# OMHOT.net
KiCad netlist of a schematic drawn in EAGLE
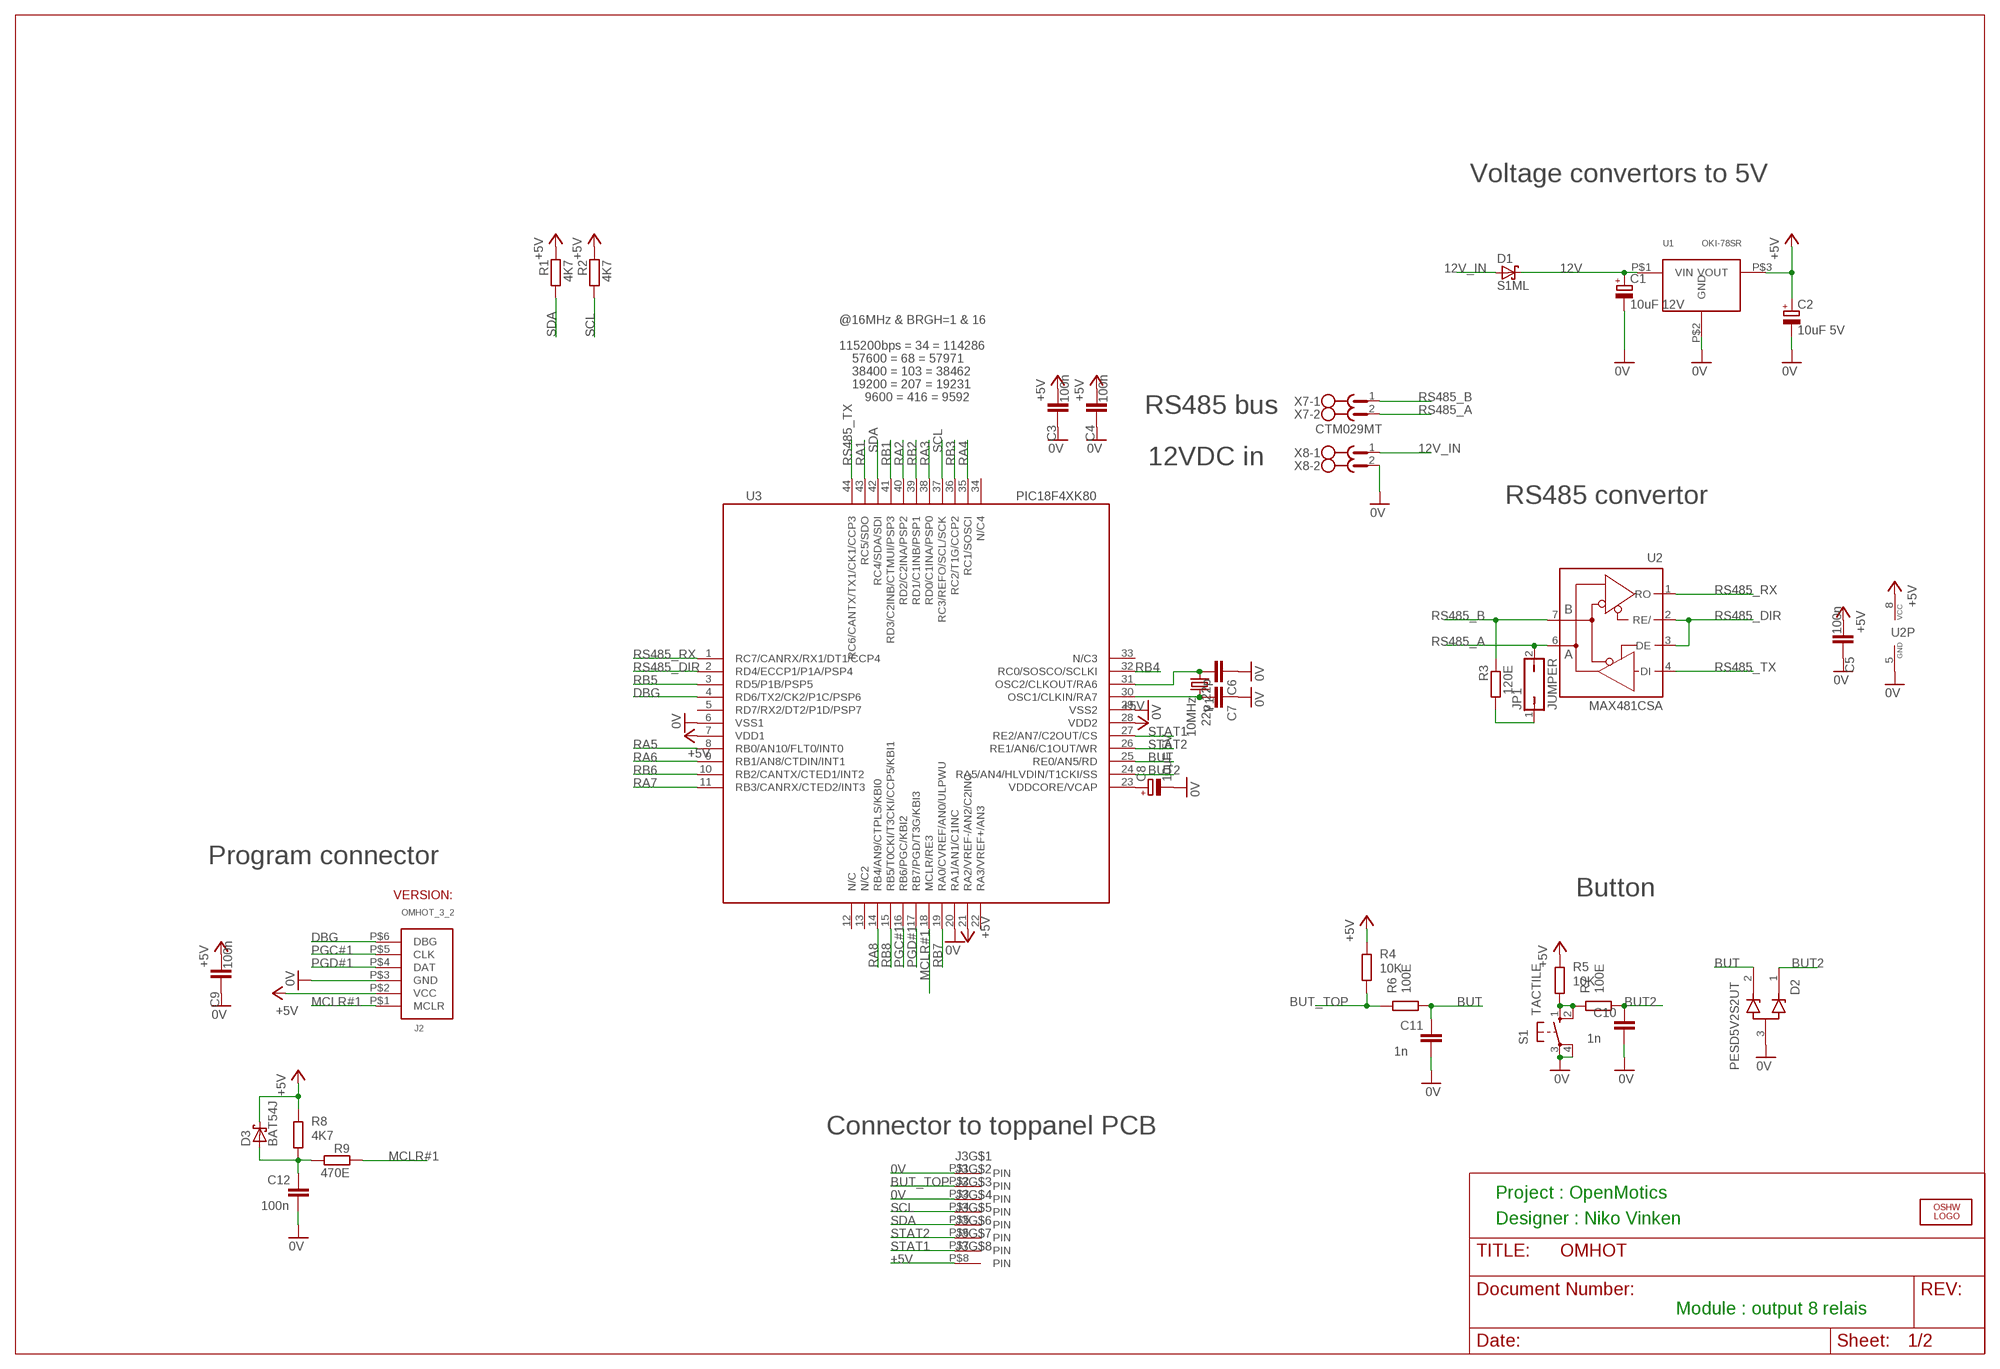
[diagram p0: schematic, sheet 1]
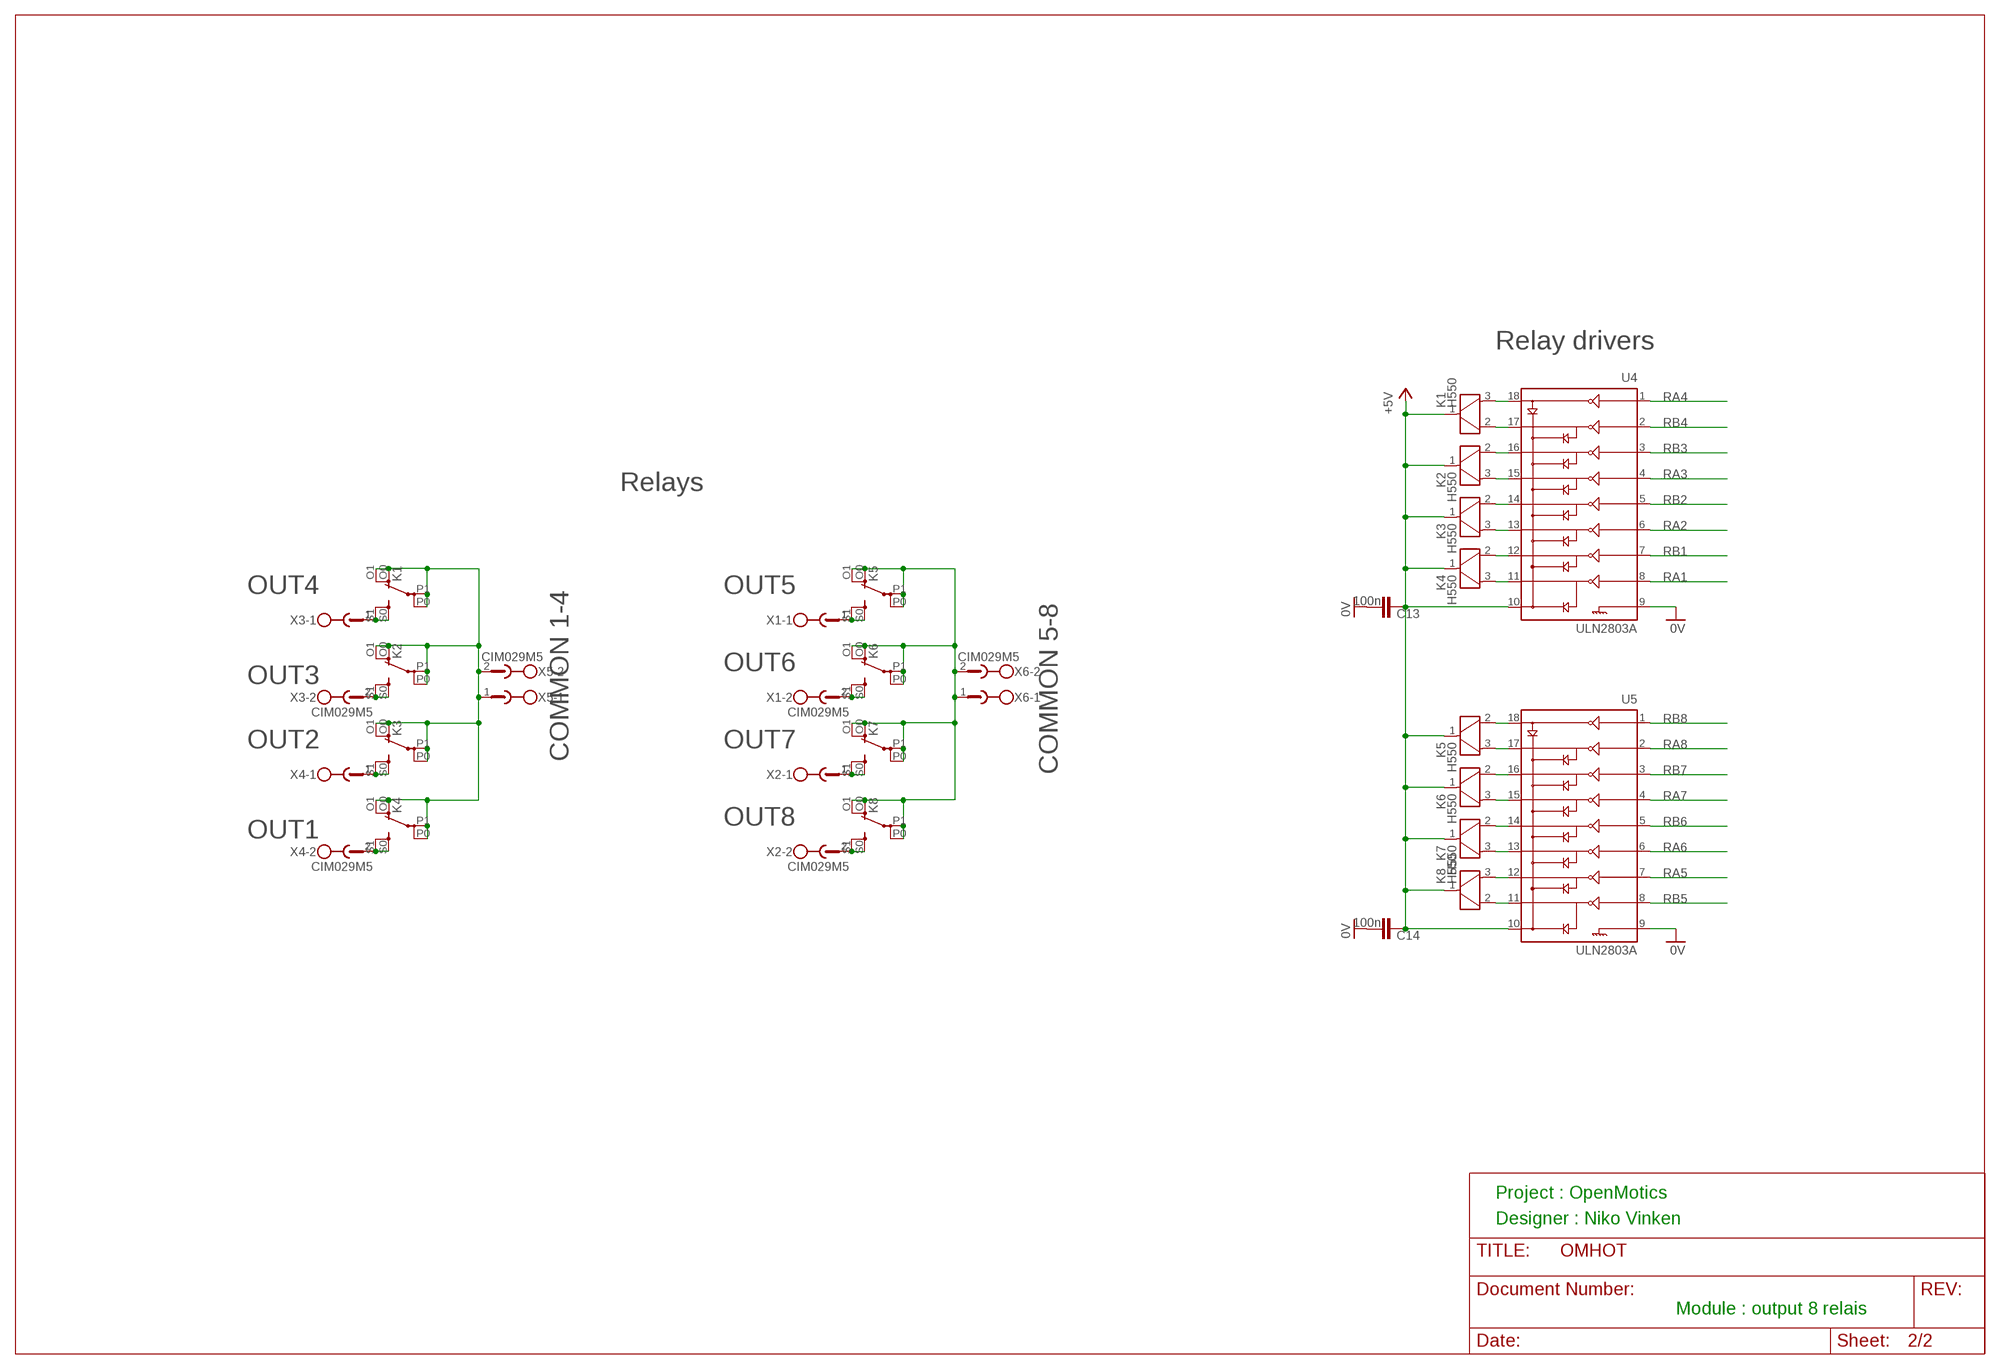
[diagram p1: schematic, sheet 2]

(export (version "E")
  (design (tool "Eeschema 10.0.6"))
  (components
    (comp (ref "C13")
      (value "100n")
      (footprint "eagle-import:C0603")
      (libsource (lib "eagle-import") (part "C-EUC0603"))
    )
    (comp (ref "C14")
      (value "100n")
      (footprint "eagle-import:C0603")
      (libsource (lib "eagle-import") (part "C-EUC0603"))
    )
    (comp (ref "K1")
      (value "H550")
      (footprint "eagle-import:H550")
      (libsource (lib "eagle-import") (part "H550"))
    )
    (comp (ref "K2")
      (value "H550")
      (footprint "eagle-import:H550")
      (libsource (lib "eagle-import") (part "H550"))
    )
    (comp (ref "K3")
      (value "H550")
      (footprint "eagle-import:H550")
      (libsource (lib "eagle-import") (part "H550"))
    )
    (comp (ref "K4")
      (value "H550")
      (footprint "eagle-import:H550")
      (libsource (lib "eagle-import") (part "H550"))
    )
    (comp (ref "K5")
      (value "H550")
      (footprint "eagle-import:H550")
      (libsource (lib "eagle-import") (part "H550"))
    )
    (comp (ref "K6")
      (value "H550")
      (footprint "eagle-import:H550")
      (libsource (lib "eagle-import") (part "H550"))
    )
    (comp (ref "K7")
      (value "H550")
      (footprint "eagle-import:H550")
      (libsource (lib "eagle-import") (part "H550"))
    )
    (comp (ref "K8")
      (value "H550")
      (footprint "eagle-import:H550")
      (libsource (lib "eagle-import") (part "H550"))
    )
    (comp (ref "U4")
      (value "ULN2803A")
      (footprint "eagle-import:SOIC18")
      (libsource (lib "eagle-import") (part "ULN2803A"))
    )
    (comp (ref "U5")
      (value "ULN2803A")
      (footprint "eagle-import:SOIC18")
      (libsource (lib "eagle-import") (part "ULN2803A"))
    )
    (comp (ref "X1")
      (value "CIM029M5")
      (footprint "eagle-import:CIM029M5")
      (fields (field (name "MF") "SAURO"))
      (libsource (lib "eagle-import") (part "CIM029M5"))
    )
    (comp (ref "X2")
      (value "CIM029M5")
      (footprint "eagle-import:CIM029M5")
      (fields (field (name "MF") "SAURO"))
      (libsource (lib "eagle-import") (part "CIM029M5"))
    )
    (comp (ref "X3")
      (value "CIM029M5")
      (footprint "eagle-import:CIM029M5")
      (fields (field (name "MF") "SAURO"))
      (libsource (lib "eagle-import") (part "CIM029M5"))
    )
    (comp (ref "X4")
      (value "CIM029M5")
      (footprint "eagle-import:CIM029M5")
      (fields (field (name "MF") "SAURO"))
      (libsource (lib "eagle-import") (part "CIM029M5"))
    )
    (comp (ref "X5")
      (value "CIM029M5")
      (footprint "eagle-import:CIM029M5")
      (fields (field (name "MF") "SAURO"))
      (libsource (lib "eagle-import") (part "CIM029M5"))
    )
    (comp (ref "X6")
      (value "CIM029M5")
      (footprint "eagle-import:CIM029M5")
      (fields (field (name "MF") "SAURO"))
      (libsource (lib "eagle-import") (part "CIM029M5"))
    )
    (comp (ref "C1")
      (value "10uF 12V")
      (footprint "eagle-import:085CS_1AR")
      (libsource (lib "eagle-import") (part "CPOL-EU085CS-1AR"))
    )
    (comp (ref "C2")
      (value "10uF 5V")
      (footprint "eagle-import:085CS_1AR")
      (libsource (lib "eagle-import") (part "CPOL-EU085CS-1AR"))
    )
    (comp (ref "C3")
      (value "100n")
      (footprint "eagle-import:C0603")
      (libsource (lib "eagle-import") (part "C-EUC0603"))
    )
    (comp (ref "C4")
      (value "100n")
      (footprint "eagle-import:C0603")
      (libsource (lib "eagle-import") (part "C-EUC0603"))
    )
    (comp (ref "C5")
      (value "100n")
      (footprint "eagle-import:C0603")
      (libsource (lib "eagle-import") (part "C-EUC0603"))
    )
    (comp (ref "C6")
      (value "22p")
      (footprint "eagle-import:C0603")
      (libsource (lib "eagle-import") (part "C-EUC0603"))
    )
    (comp (ref "C7")
      (value "22p")
      (footprint "eagle-import:C0603")
      (libsource (lib "eagle-import") (part "C-EUC0603"))
    )
    (comp (ref "C8")
      (value "10uF 5V")
      (footprint "eagle-import:085CS_1AR")
      (libsource (lib "eagle-import") (part "CPOL-EU085CS-1AR"))
    )
    (comp (ref "C9")
      (value "100n")
      (footprint "eagle-import:C0603")
      (libsource (lib "eagle-import") (part "C-EUC0603"))
    )
    (comp (ref "C10")
      (value "1n")
      (footprint "eagle-import:C0603")
      (libsource (lib "eagle-import") (part "C-EUC0603"))
    )
    (comp (ref "C11")
      (value "1n")
      (footprint "eagle-import:C0603")
      (libsource (lib "eagle-import") (part "C-EUC0603"))
    )
    (comp (ref "C12")
      (value "100n")
      (footprint "eagle-import:C0603")
      (libsource (lib "eagle-import") (part "C-EUC0603"))
    )
    (comp (ref "D1")
      (value "S1ML")
      (footprint "eagle-import:SOD123FL")
      (libsource (lib "eagle-import") (part "SMF5.0AT1"))
    )
    (comp (ref "D2")
      (value "PESD5V2S2UT")
      (footprint "eagle-import:SOT23")
      (libsource (lib "eagle-import") (part "PESD3V3S2UAT"))
    )
    (comp (ref "D3")
      (value "BAT54J")
      (footprint "eagle-import:SOD323_REFLOW")
      (libsource (lib "eagle-import") (part "BAT54J"))
    )
    (comp (ref "J2")
      (value "PROG_CON")
      (footprint "eagle-import:PROG_CON_WITH_VERSION")
      (fields (field (name "VERSION") "OMHOT_3_2"))
      (libsource (lib "eagle-import") (part "PROG_CON"))
    )
    (comp (ref "J3")
      (value "8PIN_CON_AMP")
      (footprint "eagle-import:8PIN_CON_AMP")
      (libsource (lib "eagle-import") (part "8PIN_CON_AMP"))
    )
    (comp (ref "JP1")
      (value "JUMPER")
      (footprint "eagle-import:JP1")
      (libsource (lib "eagle-import") (part "JP1Q"))
    )
    (comp (ref "LOGO2")
      (value "OSHW_LOGO_FILLX0150-NT")
      (footprint "eagle-import:OSHW_FILLX150_NOTEXT")
      (libsource (lib "eagle-import") (part "OSHW_LOGO_FILLX0150-NT"))
    )
    (comp (ref "R1")
      (value "4K7")
      (footprint "eagle-import:R0603")
      (libsource (lib "eagle-import") (part "R-EU_R0603"))
    )
    (comp (ref "R2")
      (value "4K7")
      (footprint "eagle-import:R0603")
      (libsource (lib "eagle-import") (part "R-EU_R0603"))
    )
    (comp (ref "R3")
      (value "120E")
      (footprint "eagle-import:R1206")
      (libsource (lib "eagle-import") (part "R-EU_R1206"))
    )
    (comp (ref "R4")
      (value "10K")
      (footprint "eagle-import:R0603")
      (libsource (lib "eagle-import") (part "R-EU_R0603"))
    )
    (comp (ref "R5")
      (value "10K")
      (footprint "eagle-import:R0603")
      (libsource (lib "eagle-import") (part "R-EU_R0603"))
    )
    (comp (ref "R6")
      (value "100E")
      (footprint "eagle-import:R0603")
      (libsource (lib "eagle-import") (part "R-EU_R0603"))
    )
    (comp (ref "R7")
      (value "100E")
      (footprint "eagle-import:R0603")
      (libsource (lib "eagle-import") (part "R-EU_R0603"))
    )
    (comp (ref "R8")
      (value "4K7")
      (footprint "eagle-import:R0603")
      (libsource (lib "eagle-import") (part "R-EU_R0603"))
    )
    (comp (ref "R9")
      (value "470E")
      (footprint "eagle-import:R0603")
      (libsource (lib "eagle-import") (part "R-EU_R0603"))
    )
    (comp (ref "S1")
      (value "TACTILE")
      (footprint "eagle-import:B3F-10XX")
      (fields (field (name "MPN") "B3F-1000"))
      (libsource (lib "eagle-import") (part "10-XX"))
    )
    (comp (ref "U1")
      (value "OKI-78SR")
      (footprint "eagle-import:OKI-78SR")
      (libsource (lib "eagle-import") (part "OKI-78SR"))
    )
    (comp (ref "U2")
      (value "MAX481CSA")
      (footprint "eagle-import:SO08")
      (fields (field (name "MF") "MAXIM"))
      (libsource (lib "eagle-import") (part "MAX481CSA"))
    )
    (comp (ref "U3")
      (value "PIC18F4XK80")
      (footprint "eagle-import:TQFP44")
      (libsource (lib "eagle-import") (part "PIC18F4XK80"))
    )
    (comp (ref "X7")
      (value "CTM029MT")
      (footprint "eagle-import:CTM029MT")
      (fields (field (name "MF") "SAURO"))
      (libsource (lib "eagle-import") (part "CTM029MT"))
    )
    (comp (ref "X8")
      (value "CTM029MT")
      (footprint "eagle-import:CTM029MT")
      (fields (field (name "MF") "SAURO"))
      (libsource (lib "eagle-import") (part "CTM029MT"))
    )
    (comp (ref "Y1")
      (value "10MHz")
      (footprint "eagle-import:SM49")
      (libsource (lib "eagle-import") (part "CRYSTALSM49"))
    )
  )
  (nets
    (net (code "1") (name "+5V") (class "Default")
      (node (ref "C13") (pin "2") (pinfunction "2_2") (pintype "passive"))
      (node (ref "C14") (pin "2") (pinfunction "2_2") (pintype "passive"))
      (node (ref "C2") (pin "+") (pinfunction "+_+") (pintype "passive"))
      (node (ref "C3") (pin "1") (pinfunction "1_1") (pintype "passive"))
      (node (ref "C4") (pin "1") (pinfunction "1_1") (pintype "passive"))
      (node (ref "C5") (pin "1") (pinfunction "1_1") (pintype "passive"))
      (node (ref "C9") (pin "1") (pinfunction "1_1") (pintype "passive"))
      (node (ref "D3") (pin "1") (pinfunction "1_1") (pintype "passive"))
      (node (ref "J2") (pin "P$2") (pinfunction "VCC_P$2") (pintype "bidirectional"))
      (node (ref "J3") (pin "P$8") (pinfunction "PIN_P$8") (pintype "bidirectional"))
      (node (ref "K1") (pin "1") (pinfunction "1_1") (pintype "passive"))
      (node (ref "K2") (pin "1") (pinfunction "1_1") (pintype "passive"))
      (node (ref "K3") (pin "1") (pinfunction "1_1") (pintype "passive"))
      (node (ref "K4") (pin "1") (pinfunction "1_1") (pintype "passive"))
      (node (ref "K5") (pin "1") (pinfunction "1_1") (pintype "passive"))
      (node (ref "K6") (pin "1") (pinfunction "1_1") (pintype "passive"))
      (node (ref "K7") (pin "1") (pinfunction "1_1") (pintype "passive"))
      (node (ref "K8") (pin "1") (pinfunction "1_1") (pintype "passive"))
      (node (ref "R1") (pin "1") (pinfunction "1_1") (pintype "passive"))
      (node (ref "R2") (pin "1") (pinfunction "1_1") (pintype "passive"))
      (node (ref "R4") (pin "2") (pinfunction "2_2") (pintype "passive"))
      (node (ref "R5") (pin "2") (pinfunction "2_2") (pintype "passive"))
      (node (ref "R8") (pin "2") (pinfunction "2_2") (pintype "passive"))
      (node (ref "U1") (pin "P$3") (pinfunction "VOUT_P$3") (pintype "bidirectional"))
      (node (ref "U2") (pin "8") (pinfunction "VCC_8") (pintype "power_in"))
      (node (ref "U3") (pin "21") (pinfunction "RA2/VREF-/AN2/C2INC_21") (pintype "bidirectional"))
      (node (ref "U3") (pin "28") (pinfunction "VDD2_28") (pintype "bidirectional"))
      (node (ref "U3") (pin "7") (pinfunction "VDD1_7") (pintype "bidirectional"))
      (node (ref "U4") (pin "10") (pinfunction "10_10") (pintype "bidirectional"))
      (node (ref "U5") (pin "10") (pinfunction "10_10") (pintype "bidirectional"))
    )
    (net (code "2") (name "0V") (class "Default")
      (node (ref "C1") (pin "-") (pinfunction "-_-") (pintype "passive"))
      (node (ref "C10") (pin "1") (pinfunction "1_1") (pintype "passive"))
      (node (ref "C11") (pin "1") (pinfunction "1_1") (pintype "passive"))
      (node (ref "C12") (pin "1") (pinfunction "1_1") (pintype "passive"))
      (node (ref "C13") (pin "1") (pinfunction "1_1") (pintype "passive"))
      (node (ref "C14") (pin "1") (pinfunction "1_1") (pintype "passive"))
      (node (ref "C2") (pin "-") (pinfunction "-_-") (pintype "passive"))
      (node (ref "C3") (pin "2") (pinfunction "2_2") (pintype "passive"))
      (node (ref "C4") (pin "2") (pinfunction "2_2") (pintype "passive"))
      (node (ref "C5") (pin "2") (pinfunction "2_2") (pintype "passive"))
      (node (ref "C6") (pin "1") (pinfunction "1_1") (pintype "passive"))
      (node (ref "C7") (pin "1") (pinfunction "1_1") (pintype "passive"))
      (node (ref "C8") (pin "-") (pinfunction "-_-") (pintype "passive"))
      (node (ref "C9") (pin "2") (pinfunction "2_2") (pintype "passive"))
      (node (ref "D2") (pin "3") (pinfunction "3_3") (pintype "bidirectional"))
      (node (ref "J2") (pin "P$3") (pinfunction "GND_P$3") (pintype "bidirectional"))
      (node (ref "J3") (pin "P$1") (pinfunction "PIN_P$1") (pintype "bidirectional"))
      (node (ref "J3") (pin "P$3") (pinfunction "PIN_P$3") (pintype "bidirectional"))
      (node (ref "S1") (pin "3") (pinfunction "P_3") (pintype "passive"))
      (node (ref "S1") (pin "4") (pinfunction "P1_4") (pintype "passive"))
      (node (ref "U1") (pin "P$2") (pinfunction "GND_P$2") (pintype "bidirectional"))
      (node (ref "U2") (pin "5") (pinfunction "GND_5") (pintype "power_in"))
      (node (ref "U3") (pin "20") (pinfunction "RA1/AN1/C1INC_20") (pintype "bidirectional"))
      (node (ref "U3") (pin "29") (pinfunction "VSS2_29") (pintype "bidirectional"))
      (node (ref "U3") (pin "6") (pinfunction "VSS1_6") (pintype "bidirectional"))
      (node (ref "U4") (pin "9") (pinfunction "9_9") (pintype "bidirectional"))
      (node (ref "U5") (pin "9") (pinfunction "9_9") (pintype "bidirectional"))
      (node (ref "X8") (pin "2") (pinfunction "1_2") (pintype "passive"))
    )
    (net (code "3") (name "12V") (class "Default")
      (node (ref "C1") (pin "+") (pinfunction "+_+") (pintype "passive"))
      (node (ref "D1") (pin "C") (pinfunction "C_C") (pintype "passive"))
      (node (ref "U1") (pin "P$1") (pinfunction "VIN_P$1") (pintype "bidirectional"))
    )
    (net (code "4") (name "12V_IN") (class "Default")
      (node (ref "D1") (pin "A") (pinfunction "A_A") (pintype "passive"))
      (node (ref "X8") (pin "1") (pinfunction "1_1") (pintype "passive"))
    )
    (net (code "5") (name "BUT") (class "Default")
      (node (ref "C11") (pin "2") (pinfunction "2_2") (pintype "passive"))
      (node (ref "D2") (pin "2") (pinfunction "2_2") (pintype "bidirectional"))
      (node (ref "R6") (pin "1") (pinfunction "1_1") (pintype "passive"))
      (node (ref "U3") (pin "25") (pinfunction "RE0/AN5/RD_25") (pintype "bidirectional"))
    )
    (net (code "6") (name "BUT2") (class "Default")
      (node (ref "C10") (pin "2") (pinfunction "2_2") (pintype "passive"))
      (node (ref "D2") (pin "1") (pinfunction "1_1") (pintype "bidirectional"))
      (node (ref "R7") (pin "1") (pinfunction "1_1") (pintype "passive"))
      (node (ref "U3") (pin "24") (pinfunction "RA5/AN4/HLVDIN/T1CKI/SS_24") (pintype "bidirectional"))
    )
    (net (code "7") (name "BUT_TOP") (class "Default")
      (node (ref "J3") (pin "P$2") (pinfunction "PIN_P$2") (pintype "bidirectional"))
      (node (ref "R4") (pin "1") (pinfunction "1_1") (pintype "passive"))
      (node (ref "R6") (pin "2") (pinfunction "2_2") (pintype "passive"))
    )
    (net (code "8") (name "DBG") (class "Default")
      (node (ref "J2") (pin "P$6") (pinfunction "DBG_P$6") (pintype "bidirectional"))
      (node (ref "U3") (pin "4") (pinfunction "RD6/TX2/CK2/P1C/PSP6_4") (pintype "bidirectional"))
    )
    (net (code "9") (name "MCLR#1") (class "Default")
      (node (ref "J2") (pin "P$1") (pinfunction "MCLR_P$1") (pintype "bidirectional"))
      (node (ref "R9") (pin "1") (pinfunction "1_1") (pintype "passive"))
      (node (ref "U3") (pin "18") (pinfunction "MCLR/RE3_18") (pintype "bidirectional"))
    )
    (net (code "10") (name "Net-(C12-Pad2)") (class "Default")
      (node (ref "C12") (pin "2") (pinfunction "2_2") (pintype "passive"))
      (node (ref "D3") (pin "2") (pinfunction "2_2") (pintype "passive"))
      (node (ref "R8") (pin "1") (pinfunction "1_1") (pintype "passive"))
      (node (ref "R9") (pin "2") (pinfunction "2_2") (pintype "passive"))
    )
    (net (code "11") (name "Net-(JP1-Pad1)") (class "Default")
      (node (ref "JP1") (pin "1") (pinfunction "1_1") (pintype "passive"))
      (node (ref "R3") (pin "2") (pinfunction "2_2") (pintype "passive"))
    )
    (net (code "12") (name "Net-(K1-Pad2)") (class "Default")
      (node (ref "K1") (pin "2") (pinfunction "2_2") (pintype "passive"))
      (node (ref "U4") (pin "17") (pinfunction "17_17") (pintype "bidirectional"))
    )
    (net (code "13") (name "Net-(K1-Pad3)") (class "Default")
      (node (ref "K1") (pin "3") (pinfunction "3_3") (pintype "passive"))
      (node (ref "U4") (pin "18") (pinfunction "18_18") (pintype "bidirectional"))
    )
    (net (code "14") (name "Net-(K1B-S-PadS0)") (class "Default")
      (node (ref "K1") (pin "S0") (pinfunction "S_S0") (pintype "passive"))
      (node (ref "K1") (pin "S1") (pinfunction "S_S1") (pintype "passive"))
      (node (ref "X3") (pin "1") (pinfunction "1_1") (pintype "passive"))
    )
    (net (code "15") (name "Net-(K2-Pad2)") (class "Default")
      (node (ref "K2") (pin "2") (pinfunction "2_2") (pintype "passive"))
      (node (ref "U4") (pin "16") (pinfunction "16_16") (pintype "bidirectional"))
    )
    (net (code "16") (name "Net-(K2-Pad3)") (class "Default")
      (node (ref "K2") (pin "3") (pinfunction "3_3") (pintype "passive"))
      (node (ref "U4") (pin "15") (pinfunction "15_15") (pintype "bidirectional"))
    )
    (net (code "17") (name "Net-(K3-Pad2)") (class "Default")
      (node (ref "K3") (pin "2") (pinfunction "2_2") (pintype "passive"))
      (node (ref "U4") (pin "14") (pinfunction "14_14") (pintype "bidirectional"))
    )
    (net (code "18") (name "Net-(K3-Pad3)") (class "Default")
      (node (ref "K3") (pin "3") (pinfunction "3_3") (pintype "passive"))
      (node (ref "U4") (pin "13") (pinfunction "13_13") (pintype "bidirectional"))
    )
    (net (code "19") (name "Net-(K3B-S-PadS0)") (class "Default")
      (node (ref "K3") (pin "S0") (pinfunction "S_S0") (pintype "passive"))
      (node (ref "K3") (pin "S1") (pinfunction "S_S1") (pintype "passive"))
      (node (ref "X4") (pin "1") (pinfunction "1_1") (pintype "passive"))
    )
    (net (code "20") (name "Net-(K4-Pad2)") (class "Default")
      (node (ref "K4") (pin "2") (pinfunction "2_2") (pintype "passive"))
      (node (ref "U4") (pin "12") (pinfunction "12_12") (pintype "bidirectional"))
    )
    (net (code "21") (name "Net-(K4-Pad3)") (class "Default")
      (node (ref "K4") (pin "3") (pinfunction "3_3") (pintype "passive"))
      (node (ref "U4") (pin "11") (pinfunction "11_11") (pintype "bidirectional"))
    )
    (net (code "22") (name "Net-(K5-Pad2)") (class "Default")
      (node (ref "K5") (pin "2") (pinfunction "2_2") (pintype "passive"))
      (node (ref "U5") (pin "18") (pinfunction "18_18") (pintype "bidirectional"))
    )
    (net (code "23") (name "Net-(K5-Pad3)") (class "Default")
      (node (ref "K5") (pin "3") (pinfunction "3_3") (pintype "passive"))
      (node (ref "U5") (pin "17") (pinfunction "17_17") (pintype "bidirectional"))
    )
    (net (code "24") (name "Net-(K5B-S-PadS0)") (class "Default")
      (node (ref "K5") (pin "S0") (pinfunction "S_S0") (pintype "passive"))
      (node (ref "K5") (pin "S1") (pinfunction "S_S1") (pintype "passive"))
      (node (ref "X1") (pin "1") (pinfunction "1_1") (pintype "passive"))
    )
    (net (code "25") (name "Net-(K6-Pad2)") (class "Default")
      (node (ref "K6") (pin "2") (pinfunction "2_2") (pintype "passive"))
      (node (ref "U5") (pin "16") (pinfunction "16_16") (pintype "bidirectional"))
    )
    (net (code "26") (name "Net-(K6-Pad3)") (class "Default")
      (node (ref "K6") (pin "3") (pinfunction "3_3") (pintype "passive"))
      (node (ref "U5") (pin "15") (pinfunction "15_15") (pintype "bidirectional"))
    )
    (net (code "27") (name "Net-(K7-Pad2)") (class "Default")
      (node (ref "K7") (pin "2") (pinfunction "2_2") (pintype "passive"))
      (node (ref "U5") (pin "14") (pinfunction "14_14") (pintype "bidirectional"))
    )
    (net (code "28") (name "Net-(K7-Pad3)") (class "Default")
      (node (ref "K7") (pin "3") (pinfunction "3_3") (pintype "passive"))
      (node (ref "U5") (pin "13") (pinfunction "13_13") (pintype "bidirectional"))
    )
    (net (code "29") (name "Net-(K7B-S-PadS0)") (class "Default")
      (node (ref "K7") (pin "S0") (pinfunction "S_S0") (pintype "passive"))
      (node (ref "K7") (pin "S1") (pinfunction "S_S1") (pintype "passive"))
      (node (ref "X2") (pin "1") (pinfunction "1_1") (pintype "passive"))
    )
    (net (code "30") (name "Net-(K8-Pad2)") (class "Default")
      (node (ref "K8") (pin "2") (pinfunction "2_2") (pintype "passive"))
      (node (ref "U5") (pin "11") (pinfunction "11_11") (pintype "bidirectional"))
    )
    (net (code "31") (name "Net-(K8-Pad3)") (class "Default")
      (node (ref "K8") (pin "3") (pinfunction "3_3") (pintype "passive"))
      (node (ref "U5") (pin "12") (pinfunction "12_12") (pintype "bidirectional"))
    )
    (net (code "32") (name "Net-(S1-S)") (class "Default")
      (node (ref "R5") (pin "1") (pinfunction "1_1") (pintype "passive"))
      (node (ref "R7") (pin "2") (pinfunction "2_2") (pintype "passive"))
      (node (ref "S1") (pin "1") (pinfunction "S_1") (pintype "passive"))
      (node (ref "S1") (pin "2") (pinfunction "S1_2") (pintype "passive"))
    )
    (net (code "33") (name "Net-(U3-OSC1{slash}CLKIN{slash}RA7)") (class "Default")
      (node (ref "C7") (pin "2") (pinfunction "2_2") (pintype "passive"))
      (node (ref "U3") (pin "30") (pinfunction "OSC1/CLKIN/RA7_30") (pintype "bidirectional"))
      (node (ref "Y1") (pin "2") (pinfunction "2_2") (pintype "passive"))
    )
    (net (code "34") (name "Net-(U3-OSC2{slash}CLKOUT{slash}RA6)") (class "Default")
      (node (ref "C6") (pin "2") (pinfunction "2_2") (pintype "passive"))
      (node (ref "U3") (pin "31") (pinfunction "OSC2/CLKOUT/RA6_31") (pintype "bidirectional"))
      (node (ref "Y1") (pin "1") (pinfunction "1_1") (pintype "passive"))
    )
    (net (code "35") (name "Net-(U3-VDDCORE{slash}VCAP)") (class "Default")
      (node (ref "C8") (pin "+") (pinfunction "+_+") (pintype "passive"))
      (node (ref "U3") (pin "23") (pinfunction "VDDCORE/VCAP_23") (pintype "bidirectional"))
    )
    (net (code "36") (name "Net-(X1B-1)") (class "Default")
      (node (ref "K6") (pin "S0") (pinfunction "S_S0") (pintype "passive"))
      (node (ref "K6") (pin "S1") (pinfunction "S_S1") (pintype "passive"))
      (node (ref "X1") (pin "2") (pinfunction "1_2") (pintype "passive"))
    )
    (net (code "37") (name "Net-(X2B-1)") (class "Default")
      (node (ref "K8") (pin "S0") (pinfunction "S_S0") (pintype "passive"))
      (node (ref "K8") (pin "S1") (pinfunction "S_S1") (pintype "passive"))
      (node (ref "X2") (pin "2") (pinfunction "1_2") (pintype "passive"))
    )
    (net (code "38") (name "Net-(X3B-1)") (class "Default")
      (node (ref "K2") (pin "S0") (pinfunction "S_S0") (pintype "passive"))
      (node (ref "K2") (pin "S1") (pinfunction "S_S1") (pintype "passive"))
      (node (ref "X3") (pin "2") (pinfunction "1_2") (pintype "passive"))
    )
    (net (code "39") (name "Net-(X4B-1)") (class "Default")
      (node (ref "K4") (pin "S0") (pinfunction "S_S0") (pintype "passive"))
      (node (ref "K4") (pin "S1") (pinfunction "S_S1") (pintype "passive"))
      (node (ref "X4") (pin "2") (pinfunction "1_2") (pintype "passive"))
    )
    (net (code "40") (name "Net-(X5B-1)") (class "Default")
      (node (ref "K1") (pin "O0") (pinfunction "O_O0") (pintype "passive"))
      (node (ref "K1") (pin "O1") (pinfunction "O_O1") (pintype "passive"))
      (node (ref "K1") (pin "P0") (pinfunction "P_P0") (pintype "passive"))
      (node (ref "K1") (pin "P1") (pinfunction "P_P1") (pintype "passive"))
      (node (ref "K2") (pin "O0") (pinfunction "O_O0") (pintype "passive"))
      (node (ref "K2") (pin "O1") (pinfunction "O_O1") (pintype "passive"))
      (node (ref "K2") (pin "P0") (pinfunction "P_P0") (pintype "passive"))
      (node (ref "K2") (pin "P1") (pinfunction "P_P1") (pintype "passive"))
      (node (ref "K3") (pin "O0") (pinfunction "O_O0") (pintype "passive"))
      (node (ref "K3") (pin "O1") (pinfunction "O_O1") (pintype "passive"))
      (node (ref "K3") (pin "P0") (pinfunction "P_P0") (pintype "passive"))
      (node (ref "K3") (pin "P1") (pinfunction "P_P1") (pintype "passive"))
      (node (ref "K4") (pin "O0") (pinfunction "O_O0") (pintype "passive"))
      (node (ref "K4") (pin "O1") (pinfunction "O_O1") (pintype "passive"))
      (node (ref "K4") (pin "P0") (pinfunction "P_P0") (pintype "passive"))
      (node (ref "K4") (pin "P1") (pinfunction "P_P1") (pintype "passive"))
      (node (ref "X5") (pin "1") (pinfunction "1_1") (pintype "passive"))
      (node (ref "X5") (pin "2") (pinfunction "1_2") (pintype "passive"))
    )
    (net (code "41") (name "Net-(X6B-1)") (class "Default")
      (node (ref "K5") (pin "O0") (pinfunction "O_O0") (pintype "passive"))
      (node (ref "K5") (pin "O1") (pinfunction "O_O1") (pintype "passive"))
      (node (ref "K5") (pin "P0") (pinfunction "P_P0") (pintype "passive"))
      (node (ref "K5") (pin "P1") (pinfunction "P_P1") (pintype "passive"))
      (node (ref "K6") (pin "O0") (pinfunction "O_O0") (pintype "passive"))
      (node (ref "K6") (pin "O1") (pinfunction "O_O1") (pintype "passive"))
      (node (ref "K6") (pin "P0") (pinfunction "P_P0") (pintype "passive"))
      (node (ref "K6") (pin "P1") (pinfunction "P_P1") (pintype "passive"))
      (node (ref "K7") (pin "O0") (pinfunction "O_O0") (pintype "passive"))
      (node (ref "K7") (pin "O1") (pinfunction "O_O1") (pintype "passive"))
      (node (ref "K7") (pin "P0") (pinfunction "P_P0") (pintype "passive"))
      (node (ref "K7") (pin "P1") (pinfunction "P_P1") (pintype "passive"))
      (node (ref "K8") (pin "O0") (pinfunction "O_O0") (pintype "passive"))
      (node (ref "K8") (pin "O1") (pinfunction "O_O1") (pintype "passive"))
      (node (ref "K8") (pin "P0") (pinfunction "P_P0") (pintype "passive"))
      (node (ref "K8") (pin "P1") (pinfunction "P_P1") (pintype "passive"))
      (node (ref "X6") (pin "1") (pinfunction "1_1") (pintype "passive"))
      (node (ref "X6") (pin "2") (pinfunction "1_2") (pintype "passive"))
    )
    (net (code "42") (name "PGC#1") (class "Default")
      (node (ref "J2") (pin "P$5") (pinfunction "CLK_P$5") (pintype "bidirectional"))
      (node (ref "U3") (pin "16") (pinfunction "RB6/PGC/KBI2_16") (pintype "bidirectional"))
    )
    (net (code "43") (name "PGD#1") (class "Default")
      (node (ref "J2") (pin "P$4") (pinfunction "DAT_P$4") (pintype "bidirectional"))
      (node (ref "U3") (pin "17") (pinfunction "RB7/PGD/T3G/KBI3_17") (pintype "bidirectional"))
    )
    (net (code "44") (name "RA1") (class "Default")
      (node (ref "U3") (pin "43") (pinfunction "RC5/SDO_43") (pintype "bidirectional"))
      (node (ref "U4") (pin "8") (pinfunction "8_8") (pintype "bidirectional"))
    )
    (net (code "45") (name "RA2") (class "Default")
      (node (ref "U3") (pin "40") (pinfunction "RD2/C2INA/PSP2_40") (pintype "bidirectional"))
      (node (ref "U4") (pin "6") (pinfunction "6_6") (pintype "bidirectional"))
    )
    (net (code "46") (name "RA3") (class "Default")
      (node (ref "U3") (pin "38") (pinfunction "RD0/C1INA/PSP0_38") (pintype "bidirectional"))
      (node (ref "U4") (pin "4") (pinfunction "4_4") (pintype "bidirectional"))
    )
    (net (code "47") (name "RA4") (class "Default")
      (node (ref "U3") (pin "35") (pinfunction "RC1/SOSCI_35") (pintype "bidirectional"))
      (node (ref "U4") (pin "1") (pinfunction "1_1") (pintype "bidirectional"))
    )
    (net (code "48") (name "RA5") (class "Default")
      (node (ref "U3") (pin "8") (pinfunction "RB0/AN10/FLT0/INT0_8") (pintype "bidirectional"))
      (node (ref "U5") (pin "7") (pinfunction "7_7") (pintype "bidirectional"))
    )
    (net (code "49") (name "RA6") (class "Default")
      (node (ref "U3") (pin "9") (pinfunction "RB1/AN8/CTDIN/INT1_9") (pintype "bidirectional"))
      (node (ref "U5") (pin "6") (pinfunction "6_6") (pintype "bidirectional"))
    )
    (net (code "50") (name "RA7") (class "Default")
      (node (ref "U3") (pin "11") (pinfunction "RB3/CANRX/CTED2/INT3_11") (pintype "bidirectional"))
      (node (ref "U5") (pin "4") (pinfunction "4_4") (pintype "bidirectional"))
    )
    (net (code "51") (name "RA8") (class "Default")
      (node (ref "U3") (pin "14") (pinfunction "RB4/AN9/CTPLS/KBI0_14") (pintype "bidirectional"))
      (node (ref "U5") (pin "2") (pinfunction "2_2") (pintype "bidirectional"))
    )
    (net (code "52") (name "RB1") (class "Default")
      (node (ref "U3") (pin "41") (pinfunction "RD3/C2INB/CTMUI/PSP3_41") (pintype "bidirectional"))
      (node (ref "U4") (pin "7") (pinfunction "7_7") (pintype "bidirectional"))
    )
    (net (code "53") (name "RB2") (class "Default")
      (node (ref "U3") (pin "39") (pinfunction "RD1/C1INB/PSP1_39") (pintype "bidirectional"))
      (node (ref "U4") (pin "5") (pinfunction "5_5") (pintype "bidirectional"))
    )
    (net (code "54") (name "RB3") (class "Default")
      (node (ref "U3") (pin "36") (pinfunction "RC2/T1G/CCP2_36") (pintype "bidirectional"))
      (node (ref "U4") (pin "3") (pinfunction "3_3") (pintype "bidirectional"))
    )
    (net (code "55") (name "RB4") (class "Default")
      (node (ref "U3") (pin "32") (pinfunction "RC0/SOSCO/SCLKI_32") (pintype "bidirectional"))
      (node (ref "U4") (pin "2") (pinfunction "2_2") (pintype "bidirectional"))
    )
    (net (code "56") (name "RB5") (class "Default")
      (node (ref "U3") (pin "3") (pinfunction "RD5/P1B/PSP5_3") (pintype "bidirectional"))
      (node (ref "U5") (pin "8") (pinfunction "8_8") (pintype "bidirectional"))
    )
    (net (code "57") (name "RB6") (class "Default")
      (node (ref "U3") (pin "10") (pinfunction "RB2/CANTX/CTED1/INT2_10") (pintype "bidirectional"))
      (node (ref "U5") (pin "5") (pinfunction "5_5") (pintype "bidirectional"))
    )
    (net (code "58") (name "RB7") (class "Default")
      (node (ref "U3") (pin "19") (pinfunction "RA0/CVREF/AN0/ULPWU_19") (pintype "bidirectional"))
      (node (ref "U5") (pin "3") (pinfunction "3_3") (pintype "bidirectional"))
    )
    (net (code "59") (name "RB8") (class "Default")
      (node (ref "U3") (pin "15") (pinfunction "RB5/T0CKI/T3CKI/CCP5/KBI1_15") (pintype "bidirectional"))
      (node (ref "U5") (pin "1") (pinfunction "1_1") (pintype "bidirectional"))
    )
    (net (code "60") (name "RS485_A") (class "Default")
      (node (ref "JP1") (pin "2") (pinfunction "2_2") (pintype "passive"))
      (node (ref "U2") (pin "6") (pinfunction "A_6") (pintype "passive"))
      (node (ref "X7") (pin "2") (pinfunction "1_2") (pintype "passive"))
    )
    (net (code "61") (name "RS485_B") (class "Default")
      (node (ref "R3") (pin "1") (pinfunction "1_1") (pintype "passive"))
      (node (ref "U2") (pin "7") (pinfunction "B_7") (pintype "passive"))
      (node (ref "X7") (pin "1") (pinfunction "1_1") (pintype "passive"))
    )
    (net (code "62") (name "RS485_DIR") (class "Default")
      (node (ref "U2") (pin "2") (pinfunction "RE/_2") (pintype "input"))
      (node (ref "U2") (pin "3") (pinfunction "DE_3") (pintype "input"))
      (node (ref "U3") (pin "2") (pinfunction "RD4/ECCP1/P1A/PSP4_2") (pintype "bidirectional"))
    )
    (net (code "63") (name "RS485_RX") (class "Default")
      (node (ref "U2") (pin "1") (pinfunction "RO_1") (pintype "output"))
      (node (ref "U3") (pin "1") (pinfunction "RC7/CANRX/RX1/DT1/CCP4_1") (pintype "bidirectional"))
    )
    (net (code "64") (name "RS485_TX") (class "Default")
      (node (ref "U2") (pin "4") (pinfunction "DI_4") (pintype "input"))
      (node (ref "U3") (pin "44") (pinfunction "RC6/CANTX/TX1/CK1/CCP3_44") (pintype "bidirectional"))
    )
    (net (code "65") (name "SCL") (class "Default")
      (node (ref "J3") (pin "P$4") (pinfunction "PIN_P$4") (pintype "bidirectional"))
      (node (ref "R2") (pin "2") (pinfunction "2_2") (pintype "passive"))
      (node (ref "U3") (pin "37") (pinfunction "RC3/REFO/SCL/SCK_37") (pintype "bidirectional"))
    )
    (net (code "66") (name "SDA") (class "Default")
      (node (ref "J3") (pin "P$5") (pinfunction "PIN_P$5") (pintype "bidirectional"))
      (node (ref "R1") (pin "2") (pinfunction "2_2") (pintype "passive"))
      (node (ref "U3") (pin "42") (pinfunction "RC4/SDA/SDI_42") (pintype "bidirectional"))
    )
    (net (code "67") (name "STAT1") (class "Default")
      (node (ref "J3") (pin "P$7") (pinfunction "PIN_P$7") (pintype "bidirectional"))
      (node (ref "U3") (pin "27") (pinfunction "RE2/AN7/C2OUT/CS_27") (pintype "bidirectional"))
    )
    (net (code "68") (name "STAT2") (class "Default")
      (node (ref "J3") (pin "P$6") (pinfunction "PIN_P$6") (pintype "bidirectional"))
      (node (ref "U3") (pin "26") (pinfunction "RE1/AN6/C1OUT/WR_26") (pintype "bidirectional"))
    )
    (net (code "69") (name "unconnected-(U3-N{slash}C-Pad12)") (class "Default")
      (node (ref "U3") (pin "12") (pinfunction "N/C_12") (pintype "bidirectional"))
    )
    (net (code "70") (name "unconnected-(U3-N{slash}C2-Pad13)") (class "Default")
      (node (ref "U3") (pin "13") (pinfunction "N/C2_13") (pintype "bidirectional"))
    )
    (net (code "71") (name "unconnected-(U3-N{slash}C3-Pad33)") (class "Default")
      (node (ref "U3") (pin "33") (pinfunction "N/C3_33") (pintype "bidirectional"))
    )
    (net (code "72") (name "unconnected-(U3-N{slash}C4-Pad34)") (class "Default")
      (node (ref "U3") (pin "34") (pinfunction "N/C4_34") (pintype "bidirectional"))
    )
    (net (code "73") (name "unconnected-(U3-RA3{slash}VREF+{slash}AN3-Pad22)") (class "Default")
      (node (ref "U3") (pin "22") (pinfunction "RA3/VREF+/AN3_22") (pintype "bidirectional"))
    )
    (net (code "74") (name "unconnected-(U3-RD7{slash}RX2{slash}DT2{slash}P1D{slash}PSP7-Pad5)") (class "Default")
      (node (ref "U3") (pin "5") (pinfunction "RD7/RX2/DT2/P1D/PSP7_5") (pintype "bidirectional"))
    )
  )
)
